# ip_extra.net
KiCad netlist of a schematic drawn in EAGLE
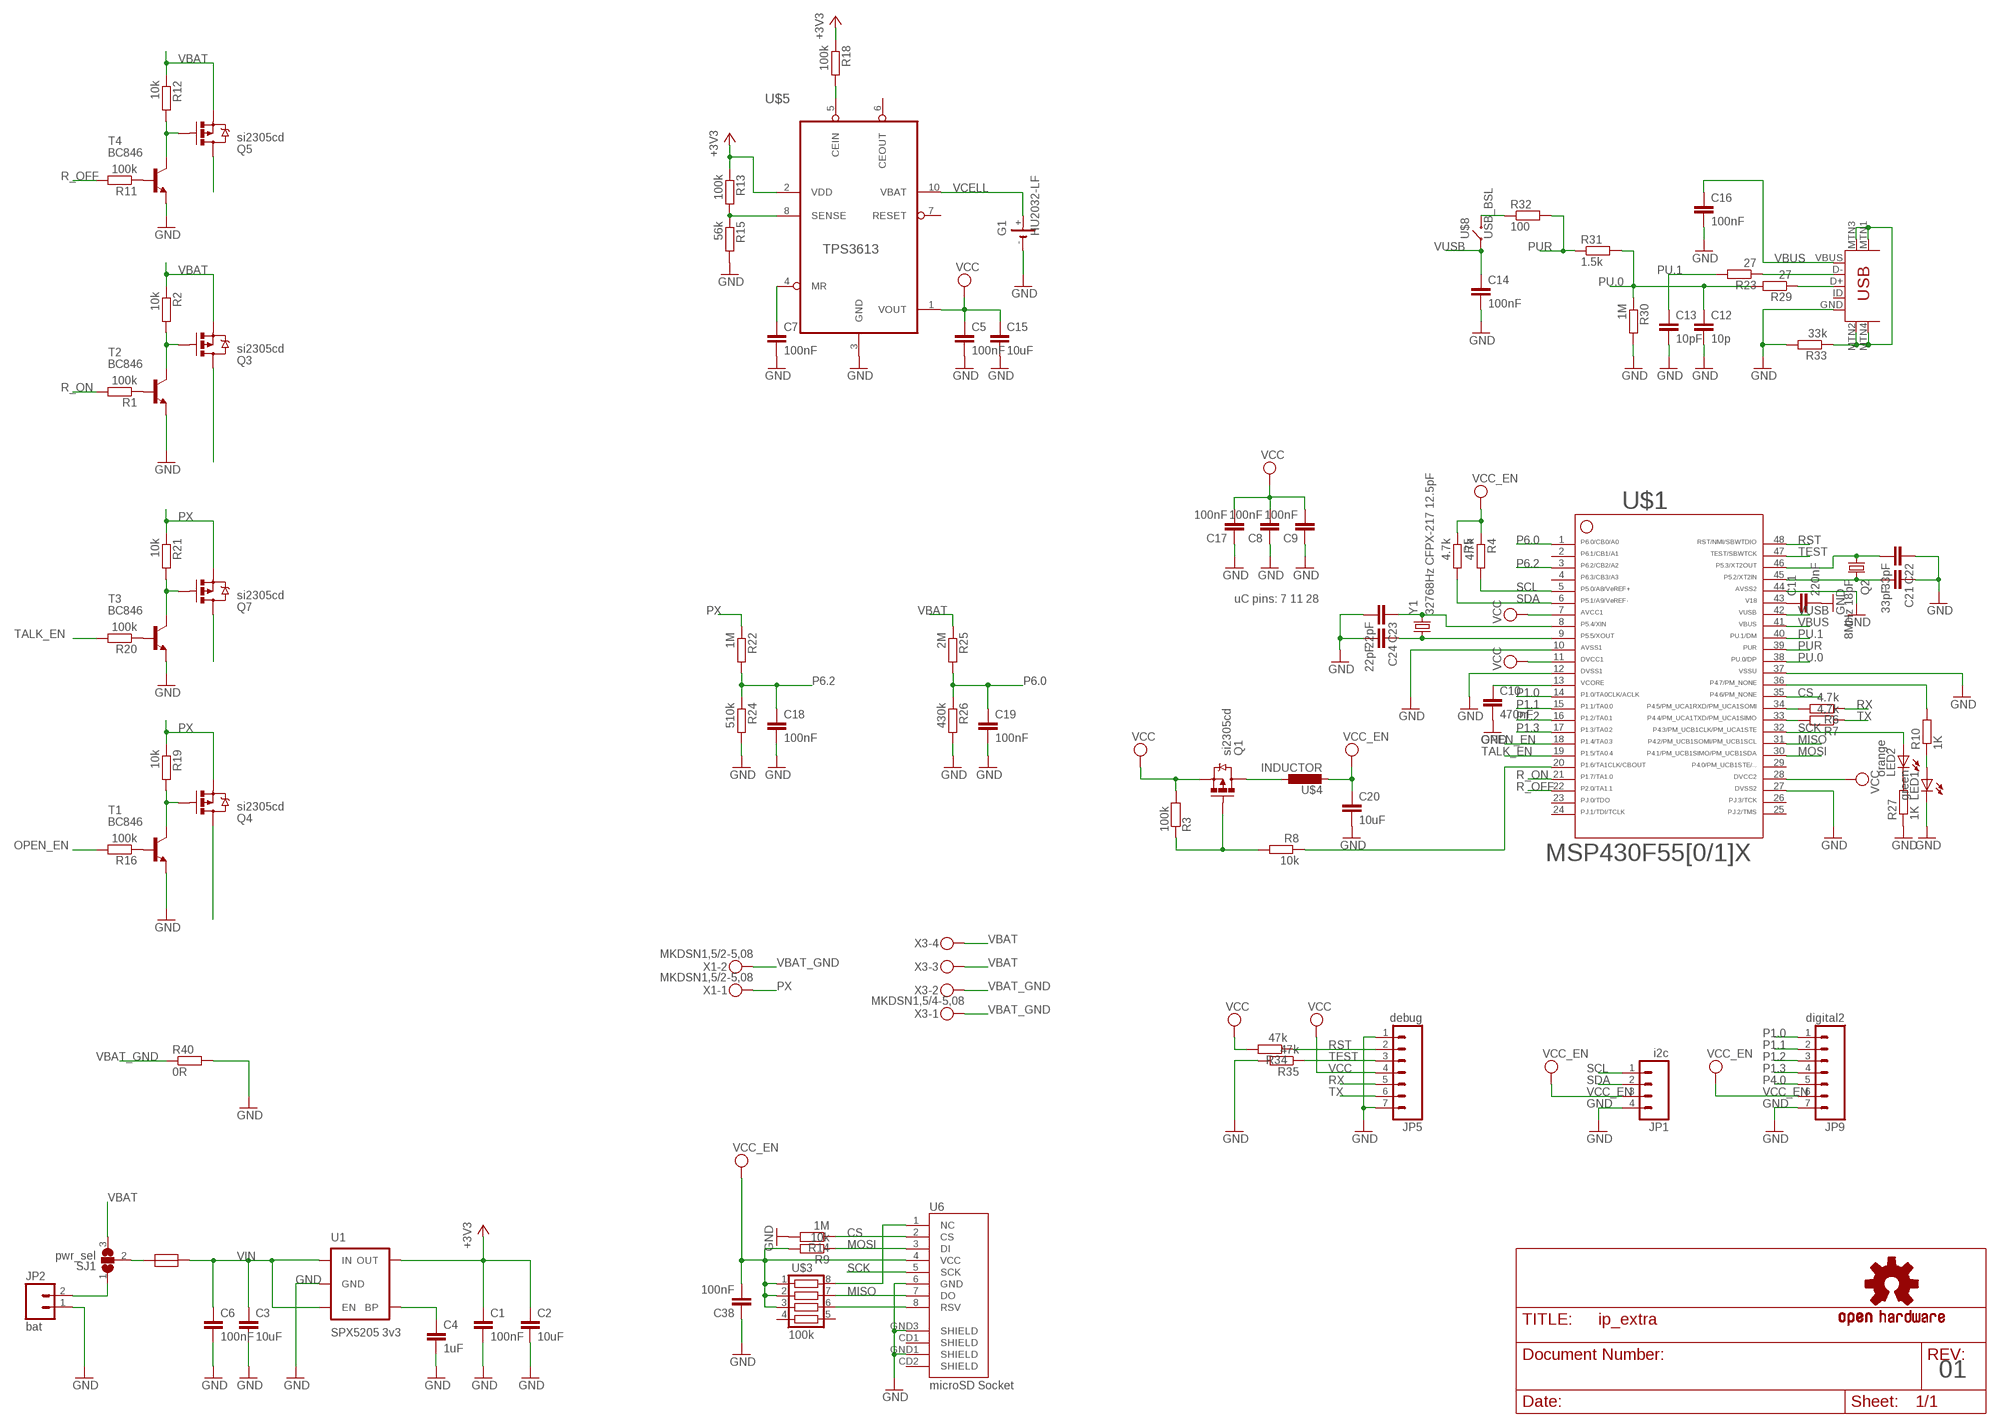
[diagram p0: schematic, sheet 1]

(export (version "E")
  (design (tool "Eeschema 10.0.6"))
  (components
    (comp (ref "C1")
      (value "100nF")
      (footprint "eagle-import:C0805")
      (libsource (lib "eagle-import") (part "C-EUC0805"))
    )
    (comp (ref "C2")
      (value "10uF")
      (footprint "eagle-import:C1206")
      (libsource (lib "eagle-import") (part "C-EUC1206"))
    )
    (comp (ref "C3")
      (value "10uF")
      (footprint "eagle-import:C1206")
      (libsource (lib "eagle-import") (part "C-EUC1206"))
    )
    (comp (ref "C4")
      (value "1uF")
      (footprint "eagle-import:C0805")
      (libsource (lib "eagle-import") (part "C-EUC0805"))
    )
    (comp (ref "C5")
      (value "100nF")
      (footprint "eagle-import:C0805")
      (libsource (lib "eagle-import") (part "C-EUC0805"))
    )
    (comp (ref "C6")
      (value "100nF")
      (footprint "eagle-import:C0805")
      (libsource (lib "eagle-import") (part "C-EUC0805"))
    )
    (comp (ref "C7")
      (value "100nF")
      (footprint "eagle-import:C0805")
      (libsource (lib "eagle-import") (part "C-EUC0805"))
    )
    (comp (ref "C8")
      (value "100nF")
      (footprint "eagle-import:C0805")
      (libsource (lib "eagle-import") (part "C-EUC0805"))
    )
    (comp (ref "C9")
      (value "100nF")
      (footprint "eagle-import:C0805")
      (libsource (lib "eagle-import") (part "C-EUC0805"))
    )
    (comp (ref "C10")
      (value "470nF")
      (footprint "eagle-import:C0805")
      (libsource (lib "eagle-import") (part "C-EUC0805"))
    )
    (comp (ref "C11")
      (value "220nF")
      (footprint "eagle-import:C0805")
      (libsource (lib "eagle-import") (part "C-EUC0805"))
    )
    (comp (ref "C12")
      (value "10p")
      (footprint "eagle-import:C0805")
      (libsource (lib "eagle-import") (part "C-EUC0805"))
    )
    (comp (ref "C13")
      (value "10pF")
      (footprint "eagle-import:C0805")
      (libsource (lib "eagle-import") (part "C-EUC0805"))
    )
    (comp (ref "C14")
      (value "100nF")
      (footprint "eagle-import:C0805")
      (libsource (lib "eagle-import") (part "C-EUC0805"))
    )
    (comp (ref "C15")
      (value "10uF")
      (footprint "eagle-import:C1206")
      (libsource (lib "eagle-import") (part "C-EUC1206"))
    )
    (comp (ref "C16")
      (value "100nF")
      (footprint "eagle-import:C0805")
      (libsource (lib "eagle-import") (part "C-EUC0805"))
    )
    (comp (ref "C17")
      (value "100nF")
      (footprint "eagle-import:C0805")
      (libsource (lib "eagle-import") (part "C-EUC0805"))
    )
    (comp (ref "C18")
      (value "100nF")
      (footprint "eagle-import:C0805")
      (libsource (lib "eagle-import") (part "C-EUC0805"))
    )
    (comp (ref "C19")
      (value "100nF")
      (footprint "eagle-import:C0805")
      (libsource (lib "eagle-import") (part "C-EUC0805"))
    )
    (comp (ref "C20")
      (value "10uF")
      (footprint "eagle-import:C1206")
      (libsource (lib "eagle-import") (part "C-EUC1206"))
    )
    (comp (ref "C21")
      (value "33pF")
      (footprint "eagle-import:C0805")
      (libsource (lib "eagle-import") (part "C-EUC0805"))
    )
    (comp (ref "C22")
      (value "33pF")
      (footprint "eagle-import:C0805")
      (libsource (lib "eagle-import") (part "C-EUC0805"))
    )
    (comp (ref "C23")
      (value "22pF")
      (footprint "eagle-import:C0805")
      (libsource (lib "eagle-import") (part "C-EUC0805"))
    )
    (comp (ref "C24")
      (value "22pF")
      (footprint "eagle-import:C0805")
      (libsource (lib "eagle-import") (part "C-EUC0805"))
    )
    (comp (ref "C38")
      (value "100nF")
      (footprint "eagle-import:C0805")
      (libsource (lib "eagle-import") (part "C-EUC0805"))
    )
    (comp (ref "G1")
      (value "HU2032-LF")
      (footprint "eagle-import:HU2032-LF")
      (libsource (lib "eagle-import") (part "HU2032-LF"))
    )
    (comp (ref "JP1")
      (value "i2c")
      (footprint "eagle-import:1X04")
      (libsource (lib "eagle-import") (part "M04PTH"))
    )
    (comp (ref "JP2")
      (value "bat")
      (footprint "eagle-import:1X02")
      (libsource (lib "eagle-import") (part "M02PTH"))
    )
    (comp (ref "JP5")
      (value "debug")
      (footprint "eagle-import:1X07")
      (libsource (lib "eagle-import") (part "M07"))
    )
    (comp (ref "JP9")
      (value "digital2")
      (footprint "eagle-import:1X07")
      (libsource (lib "eagle-import") (part "M07"))
    )
    (comp (ref "LED1")
      (value "green")
      (footprint "eagle-import:CHIP-LED0805")
      (libsource (lib "eagle-import") (part "LEDCHIP-LED0805"))
    )
    (comp (ref "LED2")
      (value "orange")
      (footprint "eagle-import:CHIP-LED0805")
      (libsource (lib "eagle-import") (part "LEDCHIP-LED0805"))
    )
    (comp (ref "Q1")
      (value "si2305cd")
      (footprint "eagle-import:SOT23-3_POWER")
      (libsource (lib "eagle-import") (part "MOSFET-PCHANNELSMD_POWER"))
    )
    (comp (ref "Q2")
      (value "8MHz 18pF")
      (footprint "eagle-import:CRYSTAL_5X3.2")
      (libsource (lib "eagle-import") (part "CRYTAL"))
    )
    (comp (ref "Q3")
      (value "si2305cd")
      (footprint "eagle-import:SOT23-3_POWER")
      (libsource (lib "eagle-import") (part "MOSFET-PCHANNELSMD_POWER"))
    )
    (comp (ref "Q4")
      (value "si2305cd")
      (footprint "eagle-import:SOT23-3_POWER")
      (libsource (lib "eagle-import") (part "MOSFET-PCHANNELSMD_POWER"))
    )
    (comp (ref "Q5")
      (value "si2305cd")
      (footprint "eagle-import:SOT23-3_POWER")
      (libsource (lib "eagle-import") (part "MOSFET-PCHANNELSMD_POWER"))
    )
    (comp (ref "Q7")
      (value "si2305cd")
      (footprint "eagle-import:SOT23-3_POWER")
      (libsource (lib "eagle-import") (part "MOSFET-PCHANNELSMD_POWER"))
    )
    (comp (ref "R1")
      (value "100k")
      (footprint "eagle-import:R0805W")
      (libsource (lib "eagle-import") (part "R-EU_R0805W"))
    )
    (comp (ref "R2")
      (value "10k")
      (footprint "eagle-import:R0805W")
      (libsource (lib "eagle-import") (part "R-EU_R0805W"))
    )
    (comp (ref "R3")
      (value "100k")
      (footprint "eagle-import:R0805W")
      (libsource (lib "eagle-import") (part "R-EU_R0805W"))
    )
    (comp (ref "R4")
      (value "4.7k")
      (footprint "eagle-import:R0805W")
      (libsource (lib "eagle-import") (part "R-EU_R0805W"))
    )
    (comp (ref "R5")
      (value "4.7k")
      (footprint "eagle-import:R0805W")
      (libsource (lib "eagle-import") (part "R-EU_R0805W"))
    )
    (comp (ref "R6")
      (value "4.7k")
      (footprint "eagle-import:R0805W")
      (libsource (lib "eagle-import") (part "R-EU_R0805W"))
    )
    (comp (ref "R7")
      (value "4.7k")
      (footprint "eagle-import:R0805W")
      (libsource (lib "eagle-import") (part "R-EU_R0805W"))
    )
    (comp (ref "R8")
      (value "10k")
      (footprint "eagle-import:R0805W")
      (libsource (lib "eagle-import") (part "R-EU_R0805W"))
    )
    (comp (ref "R9")
      (value "10k")
      (footprint "eagle-import:R0805W")
      (libsource (lib "eagle-import") (part "R-EU_R0805W"))
    )
    (comp (ref "R10")
      (value "1K")
      (footprint "eagle-import:R0805W")
      (libsource (lib "eagle-import") (part "R-EU_R0805W"))
    )
    (comp (ref "R11")
      (value "100k")
      (footprint "eagle-import:R0805W")
      (libsource (lib "eagle-import") (part "R-EU_R0805W"))
    )
    (comp (ref "R12")
      (value "10k")
      (footprint "eagle-import:R0805W")
      (libsource (lib "eagle-import") (part "R-EU_R0805W"))
    )
    (comp (ref "R13")
      (value "100k")
      (footprint "eagle-import:R0805W")
      (libsource (lib "eagle-import") (part "R-EU_R0805W"))
    )
    (comp (ref "R14")
      (value "1M")
      (footprint "eagle-import:R0805W")
      (libsource (lib "eagle-import") (part "R-EU_R0805W"))
    )
    (comp (ref "R15")
      (value "56k")
      (footprint "eagle-import:R0805W")
      (libsource (lib "eagle-import") (part "R-EU_R0805W"))
    )
    (comp (ref "R16")
      (value "100k")
      (footprint "eagle-import:R0805W")
      (libsource (lib "eagle-import") (part "R-EU_R0805W"))
    )
    (comp (ref "R18")
      (value "100k")
      (footprint "eagle-import:R0805W")
      (libsource (lib "eagle-import") (part "R-EU_R0805W"))
    )
    (comp (ref "R19")
      (value "10k")
      (footprint "eagle-import:R0805W")
      (libsource (lib "eagle-import") (part "R-EU_R0805W"))
    )
    (comp (ref "R20")
      (value "100k")
      (footprint "eagle-import:R0805W")
      (libsource (lib "eagle-import") (part "R-EU_R0805W"))
    )
    (comp (ref "R21")
      (value "10k")
      (footprint "eagle-import:R0805W")
      (libsource (lib "eagle-import") (part "R-EU_R0805W"))
    )
    (comp (ref "R22")
      (value "1M")
      (footprint "eagle-import:R0805W")
      (libsource (lib "eagle-import") (part "R-EU_R0805W"))
    )
    (comp (ref "R23")
      (value "27")
      (footprint "eagle-import:R0805W")
      (libsource (lib "eagle-import") (part "R-EU_R0805W"))
    )
    (comp (ref "R24")
      (value "510k")
      (footprint "eagle-import:R0805W")
      (libsource (lib "eagle-import") (part "R-EU_R0805W"))
    )
    (comp (ref "R25")
      (value "2M")
      (footprint "eagle-import:R0805W")
      (libsource (lib "eagle-import") (part "R-EU_R0805W"))
    )
    (comp (ref "R26")
      (value "430k")
      (footprint "eagle-import:R0805W")
      (libsource (lib "eagle-import") (part "R-EU_R0805W"))
    )
    (comp (ref "R27")
      (value "1K")
      (footprint "eagle-import:R0805W")
      (libsource (lib "eagle-import") (part "R-EU_R0805W"))
    )
    (comp (ref "R29")
      (value "27")
      (footprint "eagle-import:R0805W")
      (libsource (lib "eagle-import") (part "R-EU_R0805W"))
    )
    (comp (ref "R30")
      (value "1M")
      (footprint "eagle-import:R0805W")
      (libsource (lib "eagle-import") (part "R-EU_R0805W"))
    )
    (comp (ref "R31")
      (value "1.5k")
      (footprint "eagle-import:R0805W")
      (libsource (lib "eagle-import") (part "R-EU_R0805W"))
    )
    (comp (ref "R32")
      (value "100")
      (footprint "eagle-import:R0805W")
      (libsource (lib "eagle-import") (part "R-EU_R0805W"))
    )
    (comp (ref "R33")
      (value "33k")
      (footprint "eagle-import:R0805W")
      (libsource (lib "eagle-import") (part "R-EU_R0805W"))
    )
    (comp (ref "R34")
      (value "47k")
      (footprint "eagle-import:R0805W")
      (libsource (lib "eagle-import") (part "R-EU_R0805W"))
    )
    (comp (ref "R35")
      (value "47k")
      (footprint "eagle-import:R0805W")
      (libsource (lib "eagle-import") (part "R-EU_R0805W"))
    )
    (comp (ref "R40")
      (value "0R")
      (footprint "eagle-import:R0805W")
      (libsource (lib "eagle-import") (part "R-EU_R0805W"))
    )
    (comp (ref "SJ1")
      (value "pwr_sel")
      (footprint "eagle-import:SJ_2")
      (libsource (lib "eagle-import") (part "SJ2W"))
    )
    (comp (ref "T1")
      (value "BC846")
      (footprint "eagle-import:SOT23")
      (libsource (lib "eagle-import") (part "BC846"))
    )
    (comp (ref "T2")
      (value "BC846")
      (footprint "eagle-import:SOT23")
      (libsource (lib "eagle-import") (part "BC846"))
    )
    (comp (ref "T3")
      (value "BC846")
      (footprint "eagle-import:SOT23")
      (libsource (lib "eagle-import") (part "BC846"))
    )
    (comp (ref "T4")
      (value "BC846")
      (footprint "eagle-import:SOT23")
      (libsource (lib "eagle-import") (part "BC846"))
    )
    (comp (ref "U$1")
      (value "F55[0/1]X---PT48")
      (footprint "eagle-import:PT48")
      (libsource (lib "eagle-import") (part "F55[0/1]X---PT48"))
    )
    (comp (ref "U$2")
      (value "RESETTABLE")
      (footprint "eagle-import:1210")
      (libsource (lib "eagle-import") (part "RESETTABLE"))
    )
    (comp (ref "U$3")
      (value "100k")
      (footprint "eagle-import:YC164")
      (libsource (lib "eagle-import") (part "RES_ARR"))
    )
    (comp (ref "U$4")
      (value "INDUCTOR")
      (footprint "eagle-import:L0805W")
      (libsource (lib "eagle-import") (part "INDUCTOR"))
    )
    (comp (ref "U$5")
      (value "TPS3613")
      (footprint "eagle-import:MSOP_10P")
      (libsource (lib "eagle-import") (part "TPS3613"))
    )
    (comp (ref "U$6")
      (value "USB-MINIB-5PIN")
      (footprint "eagle-import:USB-MINIB")
      (libsource (lib "eagle-import") (part "USB-MINIB-5PIN"))
    )
    (comp (ref "U$7")
      (value "OSHW-LOGOM")
      (footprint "eagle-import:OSHW-LOGO-M")
      (libsource (lib "eagle-import") (part "OSHW-LOGOM"))
    )
    (comp (ref "U$8")
      (value "USB_BSL")
      (footprint "eagle-import:6X3.5_TACTILE_SW")
      (libsource (lib "eagle-import") (part "TACT_SW"))
    )
    (comp (ref "U1")
      (value "SPX5205 3v3")
      (footprint "eagle-import:SOT23-5")
      (libsource (lib "eagle-import") (part "V_REG_LDOSMD"))
    )
    (comp (ref "U6")
      (value "microSD Socket")
      (footprint "eagle-import:MICRO-SD-SOCKET-PP")
      (libsource (lib "eagle-import") (part "USD-SOCKETNEW"))
    )
    (comp (ref "X1")
      (value "MKDSN1,5/2-5,08")
      (footprint "eagle-import:MKDSN1,5_2-5,08")
      (fields (field (name "MPN") "MKDSN 1,5/2-5.08"))
      (libsource (lib "eagle-import") (part "MKDSN1,5/2-5,08"))
    )
    (comp (ref "X3")
      (value "MKDSN1,5/4-5,08")
      (footprint "eagle-import:MKDSN1,5_4-5,08")
      (fields (field (name "MPN") "SMKDSN1,5/4-5,08"))
      (libsource (lib "eagle-import") (part "MKDSN1,5/4-5,08"))
    )
    (comp (ref "Y1")
      (value "32768Hz CFPX-217 12.5pF")
      (footprint "eagle-import:CRYSTAL-SMD-3.2X1.5")
      (libsource (lib "eagle-import") (part "CRYSTAL3.2X1.5"))
    )
  )
  (nets
    (net (code "1") (name "+3V3") (class "Default")
      (node (ref "C1") (pin "1") (pinfunction "1_1") (pintype "passive"))
      (node (ref "C2") (pin "1") (pinfunction "1_1") (pintype "passive"))
      (node (ref "R13") (pin "1") (pinfunction "1_1") (pintype "passive"))
      (node (ref "R18") (pin "1") (pinfunction "1_1") (pintype "passive"))
      (node (ref "U$5") (pin "2") (pinfunction "VDD_2") (pintype "power_in"))
      (node (ref "U1") (pin "5") (pinfunction "OUT_5") (pintype "passive"))
    )
    (net (code "2") (name "/CS") (class "Default")
      (node (ref "R14") (pin "1") (pinfunction "1_1") (pintype "passive"))
      (node (ref "U$1") (pin "35") (pinfunction "35_35") (pintype "bidirectional"))
      (node (ref "U6") (pin "2") (pinfunction "CS_2") (pintype "bidirectional"))
    )
    (net (code "3") (name "/MISO") (class "Default")
      (node (ref "U$1") (pin "31") (pinfunction "31_31") (pintype "bidirectional"))
      (node (ref "U$3") (pin "7") (pinfunction "7_7") (pintype "passive"))
      (node (ref "U6") (pin "7") (pinfunction "DO_7") (pintype "bidirectional"))
    )
    (net (code "4") (name "/MOSI") (class "Default")
      (node (ref "R9") (pin "1") (pinfunction "1_1") (pintype "passive"))
      (node (ref "U$1") (pin "30") (pinfunction "30_30") (pintype "bidirectional"))
      (node (ref "U6") (pin "3") (pinfunction "DI_3") (pintype "bidirectional"))
    )
    (net (code "5") (name "/OPEN_EN") (class "Default")
      (node (ref "R16") (pin "2") (pinfunction "2_2") (pintype "passive"))
      (node (ref "U$1") (pin "18") (pinfunction "18_18") (pintype "bidirectional"))
    )
    (net (code "6") (name "/P1.0") (class "Default")
      (node (ref "JP9") (pin "1") (pinfunction "1_1") (pintype "passive"))
      (node (ref "U$1") (pin "14") (pinfunction "14_14") (pintype "bidirectional"))
    )
    (net (code "7") (name "/P1.1") (class "Default")
      (node (ref "JP9") (pin "2") (pinfunction "2_2") (pintype "passive"))
      (node (ref "U$1") (pin "15") (pinfunction "15_15") (pintype "bidirectional"))
    )
    (net (code "8") (name "/P1.2") (class "Default")
      (node (ref "JP9") (pin "3") (pinfunction "3_3") (pintype "passive"))
      (node (ref "U$1") (pin "16") (pinfunction "16_16") (pintype "bidirectional"))
    )
    (net (code "9") (name "/P1.3") (class "Default")
      (node (ref "JP9") (pin "4") (pinfunction "4_4") (pintype "passive"))
      (node (ref "U$1") (pin "17") (pinfunction "17_17") (pintype "bidirectional"))
    )
    (net (code "10") (name "/P4.0") (class "Default")
      (node (ref "JP9") (pin "5") (pinfunction "5_5") (pintype "passive"))
    )
    (net (code "11") (name "/P6.0") (class "Default")
      (node (ref "C19") (pin "1") (pinfunction "1_1") (pintype "passive"))
      (node (ref "R25") (pin "2") (pinfunction "2_2") (pintype "passive"))
      (node (ref "R26") (pin "1") (pinfunction "1_1") (pintype "passive"))
      (node (ref "U$1") (pin "1") (pinfunction "1_1") (pintype "bidirectional"))
    )
    (net (code "12") (name "/P6.2") (class "Default")
      (node (ref "C18") (pin "1") (pinfunction "1_1") (pintype "passive"))
      (node (ref "R22") (pin "2") (pinfunction "2_2") (pintype "passive"))
      (node (ref "R24") (pin "1") (pinfunction "1_1") (pintype "passive"))
      (node (ref "U$1") (pin "3") (pinfunction "3_3") (pintype "bidirectional"))
    )
    (net (code "13") (name "/PU.0") (class "Default")
      (node (ref "C12") (pin "1") (pinfunction "1_1") (pintype "passive"))
      (node (ref "R29") (pin "2") (pinfunction "2_2") (pintype "passive"))
      (node (ref "R30") (pin "1") (pinfunction "1_1") (pintype "passive"))
      (node (ref "R31") (pin "2") (pinfunction "2_2") (pintype "passive"))
      (node (ref "U$1") (pin "38") (pinfunction "38_38") (pintype "bidirectional"))
    )
    (net (code "14") (name "/PU.1") (class "Default")
      (node (ref "C13") (pin "1") (pinfunction "1_1") (pintype "passive"))
      (node (ref "R23") (pin "2") (pinfunction "2_2") (pintype "passive"))
      (node (ref "U$1") (pin "40") (pinfunction "40_40") (pintype "bidirectional"))
    )
    (net (code "15") (name "/PUR") (class "Default")
      (node (ref "R31") (pin "1") (pinfunction "1_1") (pintype "passive"))
      (node (ref "R32") (pin "2") (pinfunction "2_2") (pintype "passive"))
      (node (ref "U$1") (pin "39") (pinfunction "39_39") (pintype "bidirectional"))
    )
    (net (code "16") (name "/PX") (class "Default")
      (node (ref "Q4") (pin "2") (pinfunction "S_2") (pintype "passive"))
      (node (ref "Q7") (pin "2") (pinfunction "S_2") (pintype "passive"))
      (node (ref "R19") (pin "1") (pinfunction "1_1") (pintype "passive"))
      (node (ref "R21") (pin "1") (pinfunction "1_1") (pintype "passive"))
      (node (ref "R22") (pin "1") (pinfunction "1_1") (pintype "passive"))
      (node (ref "X1") (pin "1") (pinfunction "KL_1") (pintype "passive"))
    )
    (net (code "17") (name "/RST") (class "Default")
      (node (ref "JP5") (pin "2") (pinfunction "2_2") (pintype "passive"))
      (node (ref "R34") (pin "1") (pinfunction "1_1") (pintype "passive"))
      (node (ref "U$1") (pin "48") (pinfunction "48_48") (pintype "bidirectional"))
    )
    (net (code "18") (name "/RX") (class "Default")
      (node (ref "JP5") (pin "5") (pinfunction "5_5") (pintype "passive"))
      (node (ref "R6") (pin "1") (pinfunction "1_1") (pintype "passive"))
    )
    (net (code "19") (name "/R_OFF") (class "Default")
      (node (ref "R11") (pin "2") (pinfunction "2_2") (pintype "passive"))
      (node (ref "U$1") (pin "22") (pinfunction "22_22") (pintype "bidirectional"))
    )
    (net (code "20") (name "/R_ON") (class "Default")
      (node (ref "R1") (pin "2") (pinfunction "2_2") (pintype "passive"))
      (node (ref "U$1") (pin "21") (pinfunction "21_21") (pintype "bidirectional"))
    )
    (net (code "21") (name "/SCK") (class "Default")
      (node (ref "LED2") (pin "A") (pinfunction "A_A") (pintype "passive"))
      (node (ref "U$1") (pin "32") (pinfunction "32_32") (pintype "bidirectional"))
      (node (ref "U6") (pin "5") (pinfunction "SCK_5") (pintype "bidirectional"))
    )
    (net (code "22") (name "/SCL") (class "Default")
      (node (ref "JP1") (pin "1") (pinfunction "1_1") (pintype "passive"))
      (node (ref "R4") (pin "2") (pinfunction "2_2") (pintype "passive"))
      (node (ref "U$1") (pin "5") (pinfunction "5_5") (pintype "bidirectional"))
    )
    (net (code "23") (name "/SDA") (class "Default")
      (node (ref "JP1") (pin "2") (pinfunction "2_2") (pintype "passive"))
      (node (ref "R5") (pin "2") (pinfunction "2_2") (pintype "passive"))
      (node (ref "U$1") (pin "6") (pinfunction "6_6") (pintype "bidirectional"))
    )
    (net (code "24") (name "/TALK_EN") (class "Default")
      (node (ref "R20") (pin "2") (pinfunction "2_2") (pintype "passive"))
      (node (ref "U$1") (pin "19") (pinfunction "19_19") (pintype "bidirectional"))
    )
    (net (code "25") (name "/TEST") (class "Default")
      (node (ref "JP5") (pin "3") (pinfunction "3_3") (pintype "passive"))
      (node (ref "R35") (pin "1") (pinfunction "1_1") (pintype "passive"))
      (node (ref "U$1") (pin "47") (pinfunction "47_47") (pintype "input"))
    )
    (net (code "26") (name "/TX") (class "Default")
      (node (ref "JP5") (pin "6") (pinfunction "6_6") (pintype "passive"))
      (node (ref "R7") (pin "1") (pinfunction "1_1") (pintype "passive"))
    )
    (net (code "27") (name "/VBAT") (class "Default")
      (node (ref "Q3") (pin "2") (pinfunction "S_2") (pintype "passive"))
      (node (ref "Q5") (pin "2") (pinfunction "S_2") (pintype "passive"))
      (node (ref "R12") (pin "1") (pinfunction "1_1") (pintype "passive"))
      (node (ref "R2") (pin "1") (pinfunction "1_1") (pintype "passive"))
      (node (ref "R25") (pin "1") (pinfunction "1_1") (pintype "passive"))
      (node (ref "SJ1") (pin "3") (pinfunction "3_3") (pintype "passive"))
      (node (ref "X3") (pin "3") (pinfunction "KL_3") (pintype "passive"))
      (node (ref "X3") (pin "4") (pinfunction "KL_4") (pintype "passive"))
    )
    (net (code "28") (name "/VBAT_GND") (class "Default")
      (node (ref "R40") (pin "1") (pinfunction "1_1") (pintype "passive"))
      (node (ref "X1") (pin "2") (pinfunction "KL_2") (pintype "passive"))
      (node (ref "X3") (pin "1") (pinfunction "KL_1") (pintype "passive"))
      (node (ref "X3") (pin "2") (pinfunction "KL_2") (pintype "passive"))
    )
    (net (code "29") (name "/VBUS") (class "Default")
      (node (ref "C16") (pin "1") (pinfunction "1_1") (pintype "passive"))
      (node (ref "U$1") (pin "41") (pinfunction "41_41") (pintype "power_in"))
      (node (ref "U$6") (pin "VBUS") (pinfunction "VBUS_VBUS") (pintype "bidirectional"))
    )
    (net (code "30") (name "/VCELL") (class "Default")
      (node (ref "G1") (pin "+") (pinfunction "+_+") (pintype "passive"))
      (node (ref "U$5") (pin "10") (pinfunction "VBAT_10") (pintype "power_in"))
    )
    (net (code "31") (name "/VIN") (class "Default")
      (node (ref "C3") (pin "1") (pinfunction "1_1") (pintype "passive"))
      (node (ref "C6") (pin "1") (pinfunction "1_1") (pintype "passive"))
      (node (ref "U$2") (pin "P$2") (pinfunction "P$2_P$2") (pintype "bidirectional"))
      (node (ref "U1") (pin "1") (pinfunction "IN_1") (pintype "input"))
      (node (ref "U1") (pin "3") (pinfunction "EN_3") (pintype "input"))
    )
    (net (code "32") (name "/VUSB") (class "Default")
      (node (ref "C14") (pin "1") (pinfunction "1_1") (pintype "passive"))
      (node (ref "U$1") (pin "42") (pinfunction "42_42") (pintype "power_in"))
      (node (ref "U$8") (pin "1") (pinfunction "1_1") (pintype "passive"))
    )
    (net (code "33") (name "GND") (class "Default")
      (node (ref "C1") (pin "2") (pinfunction "2_2") (pintype "passive"))
      (node (ref "C10") (pin "2") (pinfunction "2_2") (pintype "passive"))
      (node (ref "C11") (pin "2") (pinfunction "2_2") (pintype "passive"))
      (node (ref "C12") (pin "2") (pinfunction "2_2") (pintype "passive"))
      (node (ref "C13") (pin "2") (pinfunction "2_2") (pintype "passive"))
      (node (ref "C14") (pin "2") (pinfunction "2_2") (pintype "passive"))
      (node (ref "C15") (pin "2") (pinfunction "2_2") (pintype "passive"))
      (node (ref "C16") (pin "2") (pinfunction "2_2") (pintype "passive"))
      (node (ref "C17") (pin "1") (pinfunction "1_1") (pintype "passive"))
      (node (ref "C18") (pin "2") (pinfunction "2_2") (pintype "passive"))
      (node (ref "C19") (pin "2") (pinfunction "2_2") (pintype "passive"))
      (node (ref "C2") (pin "2") (pinfunction "2_2") (pintype "passive"))
      (node (ref "C20") (pin "2") (pinfunction "2_2") (pintype "passive"))
      (node (ref "C21") (pin "1") (pinfunction "1_1") (pintype "passive"))
      (node (ref "C22") (pin "1") (pinfunction "1_1") (pintype "passive"))
      (node (ref "C23") (pin "2") (pinfunction "2_2") (pintype "passive"))
      (node (ref "C24") (pin "2") (pinfunction "2_2") (pintype "passive"))
      (node (ref "C3") (pin "2") (pinfunction "2_2") (pintype "passive"))
      (node (ref "C38") (pin "1") (pinfunction "1_1") (pintype "passive"))
      (node (ref "C4") (pin "2") (pinfunction "2_2") (pintype "passive"))
      (node (ref "C5") (pin "2") (pinfunction "2_2") (pintype "passive"))
      (node (ref "C6") (pin "2") (pinfunction "2_2") (pintype "passive"))
      (node (ref "C7") (pin "2") (pinfunction "2_2") (pintype "passive"))
      (node (ref "C8") (pin "1") (pinfunction "1_1") (pintype "passive"))
      (node (ref "C9") (pin "1") (pinfunction "1_1") (pintype "passive"))
      (node (ref "G1") (pin "-") (pinfunction "-_-") (pintype "passive"))
      (node (ref "JP1") (pin "4") (pinfunction "4_4") (pintype "passive"))
      (node (ref "JP2") (pin "1") (pinfunction "1_1") (pintype "passive"))
      (node (ref "JP5") (pin "1") (pinfunction "1_1") (pintype "passive"))
      (node (ref "JP5") (pin "7") (pinfunction "7_7") (pintype "passive"))
      (node (ref "JP9") (pin "7") (pinfunction "7_7") (pintype "passive"))
      (node (ref "LED1") (pin "C") (pinfunction "C_C") (pintype "passive"))
      (node (ref "R14") (pin "2") (pinfunction "2_2") (pintype "passive"))
      (node (ref "R15") (pin "2") (pinfunction "2_2") (pintype "passive"))
      (node (ref "R24") (pin "2") (pinfunction "2_2") (pintype "passive"))
      (node (ref "R26") (pin "2") (pinfunction "2_2") (pintype "passive"))
      (node (ref "R27") (pin "1") (pinfunction "1_1") (pintype "passive"))
      (node (ref "R30") (pin "2") (pinfunction "2_2") (pintype "passive"))
      (node (ref "R33") (pin "2") (pinfunction "2_2") (pintype "passive"))
      (node (ref "R35") (pin "2") (pinfunction "2_2") (pintype "passive"))
      (node (ref "R40") (pin "2") (pinfunction "2_2") (pintype "passive"))
      (node (ref "T1") (pin "2") (pinfunction "E_2") (pintype "passive"))
      (node (ref "T2") (pin "2") (pinfunction "E_2") (pintype "passive"))
      (node (ref "T3") (pin "2") (pinfunction "E_2") (pintype "passive"))
      (node (ref "T4") (pin "2") (pinfunction "E_2") (pintype "passive"))
      (node (ref "U$1") (pin "10") (pinfunction "10_10") (pintype "power_in"))
      (node (ref "U$1") (pin "12") (pinfunction "12_12") (pintype "power_in"))
      (node (ref "U$1") (pin "27") (pinfunction "27_27") (pintype "power_in"))
      (node (ref "U$1") (pin "37") (pinfunction "37_37") (pintype "power_in"))
      (node (ref "U$1") (pin "44") (pinfunction "44_44") (pintype "power_in"))
      (node (ref "U$5") (pin "3") (pinfunction "GND_3") (pintype "passive"))
      (node (ref "U$6") (pin "GND") (pinfunction "GND_GND") (pintype "bidirectional"))
      (node (ref "U1") (pin "2") (pinfunction "GND_2") (pintype "input"))
      (node (ref "U6") (pin "6") (pinfunction "GND_6") (pintype "bidirectional"))
      (node (ref "U6") (pin "GND1") (pinfunction "SHIELD_GND1") (pintype "bidirectional"))
      (node (ref "U6") (pin "GND3") (pinfunction "SHIELD_GND3") (pintype "bidirectional"))
    )
    (net (code "34") (name "Net-(C10-Pad1)") (class "Default")
      (node (ref "C10") (pin "1") (pinfunction "1_1") (pintype "passive"))
      (node (ref "U$1") (pin "13") (pinfunction "13_13") (pintype "power_in"))
    )
    (net (code "35") (name "Net-(C11-Pad1)") (class "Default")
      (node (ref "C11") (pin "1") (pinfunction "1_1") (pintype "passive"))
      (node (ref "U$1") (pin "43") (pinfunction "43_43") (pintype "power_in"))
    )
    (net (code "36") (name "Net-(JP2-Pad2)") (class "Default")
      (node (ref "JP2") (pin "2") (pinfunction "2_2") (pintype "passive"))
      (node (ref "SJ1") (pin "1") (pinfunction "1_1") (pintype "passive"))
    )
    (net (code "37") (name "Net-(LED1-PadA)") (class "Default")
      (node (ref "LED1") (pin "A") (pinfunction "A_A") (pintype "passive"))
      (node (ref "R10") (pin "1") (pinfunction "1_1") (pintype "passive"))
    )
    (net (code "38") (name "Net-(LED2-PadC)") (class "Default")
      (node (ref "LED2") (pin "C") (pinfunction "C_C") (pintype "passive"))
      (node (ref "R27") (pin "2") (pinfunction "2_2") (pintype "passive"))
    )
    (net (code "39") (name "Net-(Q1-D)") (class "Default")
      (node (ref "Q1") (pin "3") (pinfunction "D_3") (pintype "passive"))
      (node (ref "U$4") (pin "1") (pinfunction "1_1") (pintype "passive"))
    )
    (net (code "40") (name "Net-(Q1-G)") (class "Default")
      (node (ref "Q1") (pin "1") (pinfunction "G_1") (pintype "passive"))
      (node (ref "R3") (pin "1") (pinfunction "1_1") (pintype "passive"))
      (node (ref "R8") (pin "2") (pinfunction "2_2") (pintype "passive"))
    )
    (net (code "41") (name "Net-(Q2-1)") (class "Default")
      (node (ref "C22") (pin "2") (pinfunction "2_2") (pintype "passive"))
      (node (ref "Q2") (pin "P$1") (pinfunction "1_P$1") (pintype "passive"))
      (node (ref "U$1") (pin "46") (pinfunction "46_46") (pintype "power_in"))
    )
    (net (code "42") (name "Net-(Q2-2)") (class "Default")
      (node (ref "C21") (pin "2") (pinfunction "2_2") (pintype "passive"))
      (node (ref "Q2") (pin "P$2") (pinfunction "2_P$2") (pintype "passive"))
      (node (ref "U$1") (pin "45") (pinfunction "45_45") (pintype "bidirectional"))
    )
    (net (code "43") (name "Net-(Q3-G)") (class "Default")
      (node (ref "Q3") (pin "1") (pinfunction "G_1") (pintype "passive"))
      (node (ref "R2") (pin "2") (pinfunction "2_2") (pintype "passive"))
      (node (ref "T2") (pin "3") (pinfunction "C_3") (pintype "passive"))
    )
    (net (code "44") (name "Net-(Q4-G)") (class "Default")
      (node (ref "Q4") (pin "1") (pinfunction "G_1") (pintype "passive"))
      (node (ref "R19") (pin "2") (pinfunction "2_2") (pintype "passive"))
      (node (ref "T1") (pin "3") (pinfunction "C_3") (pintype "passive"))
    )
    (net (code "45") (name "Net-(Q5-G)") (class "Default")
      (node (ref "Q5") (pin "1") (pinfunction "G_1") (pintype "passive"))
      (node (ref "R12") (pin "2") (pinfunction "2_2") (pintype "passive"))
      (node (ref "T4") (pin "3") (pinfunction "C_3") (pintype "passive"))
    )
    (net (code "46") (name "Net-(Q7-G)") (class "Default")
      (node (ref "Q7") (pin "1") (pinfunction "G_1") (pintype "passive"))
      (node (ref "R21") (pin "2") (pinfunction "2_2") (pintype "passive"))
      (node (ref "T3") (pin "3") (pinfunction "C_3") (pintype "passive"))
    )
    (net (code "47") (name "Net-(R6-Pad2)") (class "Default")
      (node (ref "R6") (pin "2") (pinfunction "2_2") (pintype "passive"))
      (node (ref "U$1") (pin "34") (pinfunction "34_34") (pintype "bidirectional"))
    )
    (net (code "48") (name "Net-(R7-Pad2)") (class "Default")
      (node (ref "R7") (pin "2") (pinfunction "2_2") (pintype "passive"))
      (node (ref "U$1") (pin "33") (pinfunction "33_33") (pintype "bidirectional"))
    )
    (net (code "49") (name "Net-(R8-Pad1)") (class "Default")
      (node (ref "R8") (pin "1") (pinfunction "1_1") (pintype "passive"))
      (node (ref "U$1") (pin "20") (pinfunction "20_20") (pintype "bidirectional"))
    )
    (net (code "50") (name "Net-(R10-Pad2)") (class "Default")
      (node (ref "R10") (pin "2") (pinfunction "2_2") (pintype "passive"))
      (node (ref "U$1") (pin "36") (pinfunction "36_36") (pintype "bidirectional"))
    )
    (net (code "51") (name "Net-(R23-Pad1)") (class "Default")
      (node (ref "R23") (pin "1") (pinfunction "1_1") (pintype "passive"))
      (node (ref "U$6") (pin "D-") (pinfunction "D-_D-") (pintype "bidirectional"))
    )
    (net (code "52") (name "Net-(R29-Pad1)") (class "Default")
      (node (ref "R29") (pin "1") (pinfunction "1_1") (pintype "passive"))
      (node (ref "U$6") (pin "D+") (pinfunction "D+_D+") (pintype "bidirectional"))
    )
    (net (code "53") (name "Net-(R32-Pad1)") (class "Default")
      (node (ref "R32") (pin "1") (pinfunction "1_1") (pintype "passive"))
      (node (ref "U$8") (pin "2") (pinfunction "2_2") (pintype "passive"))
    )
    (net (code "54") (name "Net-(SJ1-Pad2)") (class "Default")
      (node (ref "SJ1") (pin "2") (pinfunction "2_2") (pintype "passive"))
      (node (ref "U$2") (pin "P$1") (pinfunction "P$1_P$1") (pintype "bidirectional"))
    )
    (net (code "55") (name "Net-(T1-B)") (class "Default")
      (node (ref "R16") (pin "1") (pinfunction "1_1") (pintype "passive"))
      (node (ref "T1") (pin "1") (pinfunction "B_1") (pintype "passive"))
    )
    (net (code "56") (name "Net-(T2-B)") (class "Default")
      (node (ref "R1") (pin "1") (pinfunction "1_1") (pintype "passive"))
      (node (ref "T2") (pin "1") (pinfunction "B_1") (pintype "passive"))
    )
    (net (code "57") (name "Net-(T3-B)") (class "Default")
      (node (ref "R20") (pin "1") (pinfunction "1_1") (pintype "passive"))
      (node (ref "T3") (pin "1") (pinfunction "B_1") (pintype "passive"))
    )
    (net (code "58") (name "Net-(T4-B)") (class "Default")
      (node (ref "R11") (pin "1") (pinfunction "1_1") (pintype "passive"))
      (node (ref "T4") (pin "1") (pinfunction "B_1") (pintype "passive"))
    )
    (net (code "59") (name "Net-(U$5-CEIN)") (class "Default")
      (node (ref "R18") (pin "2") (pinfunction "2_2") (pintype "passive"))
      (node (ref "U$5") (pin "5") (pinfunction "CEIN_5") (pintype "input"))
    )
    (net (code "60") (name "Net-(U$5-MR)") (class "Default")
      (node (ref "C7") (pin "1") (pinfunction "1_1") (pintype "passive"))
      (node (ref "U$5") (pin "4") (pinfunction "MR_4") (pintype "input"))
    )
    (net (code "61") (name "Net-(U$5-SENSE)") (class "Default")
      (node (ref "R13") (pin "2") (pinfunction "2_2") (pintype "passive"))
      (node (ref "R15") (pin "1") (pinfunction "1_1") (pintype "passive"))
      (node (ref "U$5") (pin "8") (pinfunction "SENSE_8") (pintype "input"))
    )
    (net (code "62") (name "Net-(U$6-MTN1)") (class "Default")
      (node (ref "R33") (pin "1") (pinfunction "1_1") (pintype "passive"))
      (node (ref "U$6") (pin "MTN1") (pinfunction "MTN2_MTN1") (pintype "bidirectional"))
      (node (ref "U$6") (pin "MTN2") (pinfunction "MTN3_MTN2") (pintype "bidirectional"))
      (node (ref "U$6") (pin "MTN3") (pinfunction "MTN1_MTN3") (pintype "bidirectional"))
      (node (ref "U$6") (pin "MTN4") (pinfunction "MTN4_MTN4") (pintype "bidirectional"))
    )
    (net (code "63") (name "Net-(U1-BP)") (class "Default")
      (node (ref "C4") (pin "1") (pinfunction "1_1") (pintype "passive"))
      (node (ref "U1") (pin "4") (pinfunction "BP_4") (pintype "input"))
    )
    (net (code "64") (name "Net-(U6-NC)") (class "Default")
      (node (ref "U$3") (pin "8") (pinfunction "8_8") (pintype "passive"))
      (node (ref "U6") (pin "1") (pinfunction "NC_1") (pintype "bidirectional"))
    )
    (net (code "65") (name "Net-(U6-RSV)") (class "Default")
      (node (ref "U$3") (pin "6") (pinfunction "6_6") (pintype "passive"))
      (node (ref "U6") (pin "8") (pinfunction "RSV_8") (pintype "bidirectional"))
    )
    (net (code "66") (name "Net-(Y1-1)") (class "Default")
      (node (ref "C24") (pin "1") (pinfunction "1_1") (pintype "passive"))
      (node (ref "U$1") (pin "9") (pinfunction "9_9") (pintype "bidirectional"))
      (node (ref "Y1") (pin "P$1") (pinfunction "1_P$1") (pintype "passive"))
    )
    (net (code "67") (name "Net-(Y1-2)") (class "Default")
      (node (ref "C23") (pin "1") (pinfunction "1_1") (pintype "passive"))
      (node (ref "U$1") (pin "8") (pinfunction "8_8") (pintype "bidirectional"))
      (node (ref "Y1") (pin "P$2") (pinfunction "2_P$2") (pintype "passive"))
    )
    (net (code "68") (name "VCC") (class "Default")
      (node (ref "C15") (pin "1") (pinfunction "1_1") (pintype "passive"))
      (node (ref "C17") (pin "2") (pinfunction "2_2") (pintype "passive"))
      (node (ref "C5") (pin "1") (pinfunction "1_1") (pintype "passive"))
      (node (ref "C8") (pin "2") (pinfunction "2_2") (pintype "passive"))
      (node (ref "C9") (pin "2") (pinfunction "2_2") (pintype "passive"))
      (node (ref "JP5") (pin "4") (pinfunction "4_4") (pintype "passive"))
      (node (ref "Q1") (pin "2") (pinfunction "S_2") (pintype "passive"))
      (node (ref "R3") (pin "2") (pinfunction "2_2") (pintype "passive"))
      (node (ref "R34") (pin "2") (pinfunction "2_2") (pintype "passive"))
      (node (ref "U$1") (pin "11") (pinfunction "11_11") (pintype "power_in"))
      (node (ref "U$1") (pin "28") (pinfunction "28_28") (pintype "power_in"))
      (node (ref "U$1") (pin "7") (pinfunction "7_7") (pintype "power_in"))
      (node (ref "U$5") (pin "1") (pinfunction "VOUT_1") (pintype "power_in"))
    )
    (net (code "69") (name "VCC_EN") (class "Default")
      (node (ref "C20") (pin "1") (pinfunction "1_1") (pintype "passive"))
      (node (ref "C38") (pin "2") (pinfunction "2_2") (pintype "passive"))
      (node (ref "JP1") (pin "3") (pinfunction "3_3") (pintype "passive"))
      (node (ref "JP9") (pin "6") (pinfunction "6_6") (pintype "passive"))
      (node (ref "R4") (pin "1") (pinfunction "1_1") (pintype "passive"))
      (node (ref "R5") (pin "1") (pinfunction "1_1") (pintype "passive"))
      (node (ref "R9") (pin "2") (pinfunction "2_2") (pintype "passive"))
      (node (ref "U$3") (pin "1") (pinfunction "1_1") (pintype "passive"))
      (node (ref "U$3") (pin "2") (pinfunction "2_2") (pintype "passive"))
      (node (ref "U$3") (pin "3") (pinfunction "3_3") (pintype "passive"))
      (node (ref "U$4") (pin "2") (pinfunction "2_2") (pintype "passive"))
      (node (ref "U6") (pin "4") (pinfunction "VCC_4") (pintype "bidirectional"))
    )
    (net (code "70") (name "unconnected-(G1-+-Pad+@1)") (class "Default")
      (node (ref "G1") (pin "+@1") (pinfunction "+_+@1") (pintype "passive"))
    )
    (net (code "71") (name "unconnected-(Q3-D-Pad3)") (class "Default")
      (node (ref "Q3") (pin "3") (pinfunction "D_3") (pintype "passive"))
    )
    (net (code "72") (name "unconnected-(Q4-D-Pad3)") (class "Default")
      (node (ref "Q4") (pin "3") (pinfunction "D_3") (pintype "passive"))
    )
    (net (code "73") (name "unconnected-(Q5-D-Pad3)") (class "Default")
      (node (ref "Q5") (pin "3") (pinfunction "D_3") (pintype "passive"))
    )
    (net (code "74") (name "unconnected-(Q7-D-Pad3)") (class "Default")
      (node (ref "Q7") (pin "3") (pinfunction "D_3") (pintype "passive"))
    )
    (net (code "75") (name "unconnected-(U$1-Pad2)") (class "Default")
      (node (ref "U$1") (pin "2") (pinfunction "2_2") (pintype "bidirectional"))
    )
    (net (code "76") (name "unconnected-(U$1-Pad4)") (class "Default")
      (node (ref "U$1") (pin "4") (pinfunction "4_4") (pintype "bidirectional"))
    )
    (net (code "77") (name "unconnected-(U$1-Pad23)") (class "Default")
      (node (ref "U$1") (pin "23") (pinfunction "23_23") (pintype "bidirectional"))
    )
    (net (code "78") (name "unconnected-(U$1-Pad24)") (class "Default")
      (node (ref "U$1") (pin "24") (pinfunction "24_24") (pintype "bidirectional"))
    )
    (net (code "79") (name "unconnected-(U$1-Pad25)") (class "Default")
      (node (ref "U$1") (pin "25") (pinfunction "25_25") (pintype "bidirectional"))
    )
    (net (code "80") (name "unconnected-(U$1-Pad26)") (class "Default")
      (node (ref "U$1") (pin "26") (pinfunction "26_26") (pintype "bidirectional"))
    )
    (net (code "81") (name "unconnected-(U$1-Pad29)") (class "Default")
      (node (ref "U$1") (pin "29") (pinfunction "29_29") (pintype "bidirectional"))
    )
    (net (code "82") (name "unconnected-(U$3-Pad4)") (class "Default")
      (node (ref "U$3") (pin "4") (pinfunction "4_4") (pintype "passive"))
    )
    (net (code "83") (name "unconnected-(U$3-Pad5)") (class "Default")
      (node (ref "U$3") (pin "5") (pinfunction "5_5") (pintype "passive"))
    )
    (net (code "84") (name "unconnected-(U$5-CEOUT-Pad6)") (class "Default")
      (node (ref "U$5") (pin "6") (pinfunction "CEOUT_6") (pintype "output"))
    )
    (net (code "85") (name "unconnected-(U$5-RESET-Pad7)") (class "Default")
      (node (ref "U$5") (pin "7") (pinfunction "RESET_7") (pintype "output"))
    )
    (net (code "86") (name "unconnected-(U$6-PadID)") (class "Default")
      (node (ref "U$6") (pin "ID") (pinfunction "ID_ID") (pintype "bidirectional"))
    )
    (net (code "87") (name "unconnected-(U6-SHIELD-PadCD1)") (class "Default")
      (node (ref "U6") (pin "CD1") (pinfunction "SHIELD_CD1") (pintype "bidirectional"))
    )
    (net (code "88") (name "unconnected-(U6-SHIELD-PadCD2)") (class "Default")
      (node (ref "U6") (pin "CD2") (pinfunction "SHIELD_CD2") (pintype "bidirectional"))
    )
  )
)
